# amplifier_modified2.net
KiCad netlist of a schematic drawn in EAGLE
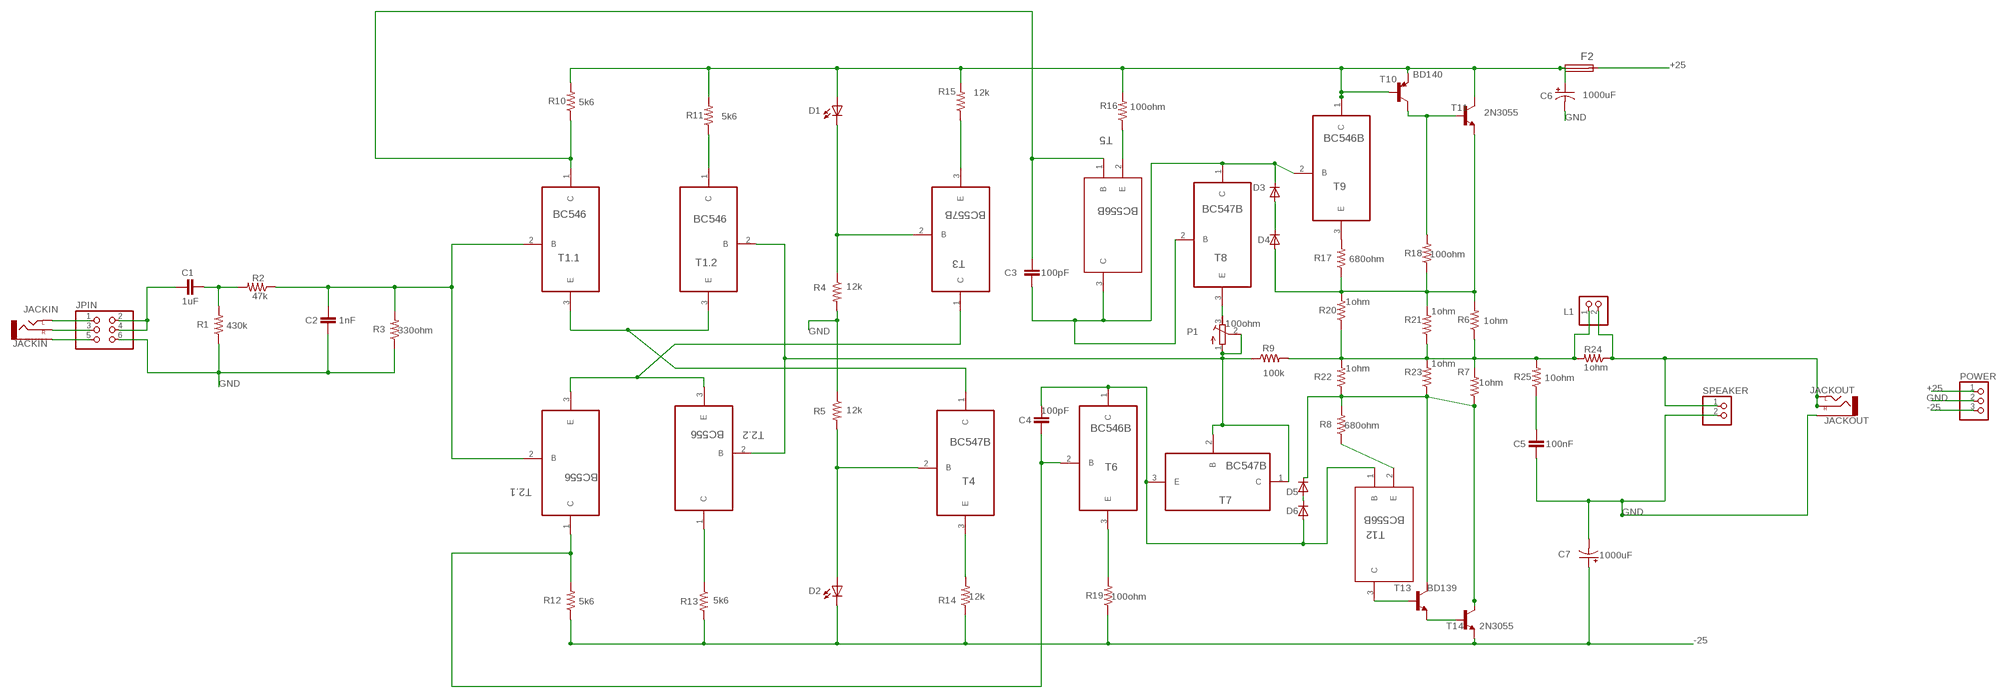
[diagram p0: schematic, sheet 1]

(export (version "E")
  (design (tool "Eeschema 10.0.6"))
  (components
    (comp (ref "C1")
      (value "1uF")
      (footprint "eagle-import:CAP-PTH-5MM")
      (libsource (lib "eagle-import") (part "CAPPTH1"))
    )
    (comp (ref "C2")
      (value "1nF")
      (footprint "eagle-import:CAP-PTH-5MM")
      (libsource (lib "eagle-import") (part "CAPPTH1"))
    )
    (comp (ref "C3")
      (value "100pF")
      (footprint "eagle-import:C5B3")
      (libsource (lib "eagle-import") (part "C5/3"))
    )
    (comp (ref "C4")
      (value "100pF")
      (footprint "eagle-import:C5B3")
      (libsource (lib "eagle-import") (part "C5/3"))
    )
    (comp (ref "C5")
      (value "100nF")
      (footprint "eagle-import:C5B3")
      (libsource (lib "eagle-import") (part "C5/3"))
    )
    (comp (ref "C6")
      (value "1000uF")
      (footprint "eagle-import:E5-6")
      (libsource (lib "eagle-import") (part "CPOL-USE5-6"))
    )
    (comp (ref "C7")
      (value "1000uF")
      (footprint "eagle-import:E5-6")
      (libsource (lib "eagle-import") (part "CPOL-USE5-6"))
    )
    (comp (ref "D1")
      (value "LED5MM")
      (footprint "eagle-import:LED5MM")
      (libsource (lib "eagle-import") (part "LED5MM"))
    )
    (comp (ref "D2")
      (value "LED5MM")
      (footprint "eagle-import:LED5MM")
      (libsource (lib "eagle-import") (part "LED5MM"))
    )
    (comp (ref "D3")
      (value "1N4148DO35-10")
      (footprint "eagle-import:DO35-10")
      (libsource (lib "eagle-import") (part "1N4148DO35-10"))
    )
    (comp (ref "D4")
      (value "1N4148DO35-10")
      (footprint "eagle-import:DO35-10")
      (libsource (lib "eagle-import") (part "1N4148DO35-10"))
    )
    (comp (ref "D5")
      (value "1N4148DO35-10")
      (footprint "eagle-import:DO35-10")
      (libsource (lib "eagle-import") (part "1N4148DO35-10"))
    )
    (comp (ref "D6")
      (value "1N4148DO35-10")
      (footprint "eagle-import:DO35-10")
      (libsource (lib "eagle-import") (part "1N4148DO35-10"))
    )
    (comp (ref "F2")
      (value "FUSEBLANK_5X20MM")
      (footprint "eagle-import:FUSE_HOLDER_5X20MM")
      (fields (field (name "OC_FARNELL") "unknown") (field (name "OC_NEWARK") "unknown"))
      (libsource (lib "eagle-import") (part "FUSEBLANK_5X20MM"))
    )
    (comp (ref "JACKIN")
      (value "JACKIN")
      (footprint "eagle-import:STEREOJACK2.5MM_STEREOJACK2.5MM")
      (libsource (lib "eagle-import") (part "AUDIO-JACK2.5MM"))
    )
    (comp (ref "JACKOUT")
      (value "JACKOUT")
      (footprint "eagle-import:STEREOJACK2.5MM_STEREOJACK2.5MM")
      (libsource (lib "eagle-import") (part "AUDIO-JACK2.5MM"))
    )
    (comp (ref "JPIN")
      (value "PINHD-2X3/90")
      (footprint "eagle-import:2X03_90")
      (libsource (lib "eagle-import") (part "PINHD-2X3/90"))
    )
    (comp (ref "L1")
      (value "PINHD-1X2/90")
      (footprint "eagle-import:1X02_90")
      (libsource (lib "eagle-import") (part "PINHD-1X2/90"))
    )
    (comp (ref "P1")
      (value "100ohm")
      (footprint "eagle-import:RTRIM74X")
      (libsource (lib "eagle-import") (part "R-TRIMM74X"))
    )
    (comp (ref "POWER")
      (value "PINHD-1X3/90")
      (footprint "eagle-import:1X03_90")
      (libsource (lib "eagle-import") (part "PINHD-1X3/90"))
    )
    (comp (ref "R1")
      (value "430k")
      (footprint "eagle-import:AXIAL-0.8")
      (libsource (lib "eagle-import") (part "SparkFun-Resistors_RESISTORPTH-2W"))
    )
    (comp (ref "R2")
      (value "47k")
      (footprint "eagle-import:AXIAL-0.8")
      (libsource (lib "eagle-import") (part "SparkFun-Resistors_RESISTORPTH-2W"))
    )
    (comp (ref "R3")
      (value "330ohm")
      (footprint "eagle-import:AXIAL-0.8")
      (libsource (lib "eagle-import") (part "SparkFun-Resistors_RESISTORPTH-2W"))
    )
    (comp (ref "R4")
      (value "12k")
      (footprint "eagle-import:AXIAL-0.8")
      (libsource (lib "eagle-import") (part "SparkFun-Resistors_RESISTORPTH-2W"))
    )
    (comp (ref "R5")
      (value "12k")
      (footprint "eagle-import:AXIAL-0.8")
      (libsource (lib "eagle-import") (part "SparkFun-Resistors_RESISTORPTH-2W"))
    )
    (comp (ref "R6")
      (value "1ohm")
      (footprint "eagle-import:AXIAL-0.8")
      (libsource (lib "eagle-import") (part "RESISTORPTH-2W"))
    )
    (comp (ref "R7")
      (value "1ohm")
      (footprint "eagle-import:AXIAL-0.8")
      (libsource (lib "eagle-import") (part "RESISTORPTH-2W"))
    )
    (comp (ref "R8")
      (value "680ohm")
      (footprint "eagle-import:AXIAL-0.8")
      (libsource (lib "eagle-import") (part "SparkFun-Resistors_RESISTORPTH-2W"))
    )
    (comp (ref "R9")
      (value "100k")
      (footprint "eagle-import:AXIAL-0.8")
      (libsource (lib "eagle-import") (part "SparkFun-Resistors_RESISTORPTH-2W"))
    )
    (comp (ref "R10")
      (value "5k6")
      (footprint "eagle-import:AXIAL-0.8")
      (libsource (lib "eagle-import") (part "SparkFun-Resistors_RESISTORPTH-2W"))
    )
    (comp (ref "R11")
      (value "5k6")
      (footprint "eagle-import:AXIAL-0.8")
      (libsource (lib "eagle-import") (part "SparkFun-Resistors_RESISTORPTH-2W"))
    )
    (comp (ref "R12")
      (value "5k6")
      (footprint "eagle-import:AXIAL-0.8")
      (libsource (lib "eagle-import") (part "SparkFun-Resistors_RESISTORPTH-2W"))
    )
    (comp (ref "R13")
      (value "5k6")
      (footprint "eagle-import:AXIAL-0.8")
      (libsource (lib "eagle-import") (part "SparkFun-Resistors_RESISTORPTH-2W"))
    )
    (comp (ref "R14")
      (value "12k")
      (footprint "eagle-import:AXIAL-0.8")
      (libsource (lib "eagle-import") (part "SparkFun-Resistors_RESISTORPTH-2W"))
    )
    (comp (ref "R15")
      (value "12k")
      (footprint "eagle-import:AXIAL-0.8")
      (libsource (lib "eagle-import") (part "SparkFun-Resistors_RESISTORPTH-2W"))
    )
    (comp (ref "R16")
      (value "100ohm")
      (footprint "eagle-import:AXIAL-0.8")
      (libsource (lib "eagle-import") (part "SparkFun-Resistors_RESISTORPTH-2W"))
    )
    (comp (ref "R17")
      (value "680ohm")
      (footprint "eagle-import:AXIAL-0.8")
      (libsource (lib "eagle-import") (part "SparkFun-Resistors_RESISTORPTH-2W"))
    )
    (comp (ref "R18")
      (value "100ohm")
      (footprint "eagle-import:AXIAL-0.8")
      (libsource (lib "eagle-import") (part "SparkFun-Resistors_RESISTORPTH-2W"))
    )
    (comp (ref "R19")
      (value "100ohm")
      (footprint "eagle-import:AXIAL-0.8")
      (libsource (lib "eagle-import") (part "SparkFun-Resistors_RESISTORPTH-2W"))
    )
    (comp (ref "R20")
      (value "1ohm")
      (footprint "eagle-import:AXIAL-0.8")
      (libsource (lib "eagle-import") (part "RESISTORPTH-2W"))
    )
    (comp (ref "R21")
      (value "1ohm")
      (footprint "eagle-import:AXIAL-0.8")
      (libsource (lib "eagle-import") (part "RESISTORPTH-2W"))
    )
    (comp (ref "R22")
      (value "1ohm")
      (footprint "eagle-import:AXIAL-0.8")
      (libsource (lib "eagle-import") (part "RESISTORPTH-2W"))
    )
    (comp (ref "R23")
      (value "1ohm")
      (footprint "eagle-import:AXIAL-0.8")
      (libsource (lib "eagle-import") (part "RESISTORPTH-2W"))
    )
    (comp (ref "R24")
      (value "1ohm")
      (footprint "eagle-import:AXIAL-0.8")
      (libsource (lib "eagle-import") (part "RESISTORPTH-2W"))
    )
    (comp (ref "R25")
      (value "10ohm")
      (footprint "eagle-import:AXIAL-0.8")
      (libsource (lib "eagle-import") (part "SparkFun-Resistors_RESISTORPTH-2W"))
    )
    (comp (ref "SPEAKER")
      (value "PINHD-1X2/90")
      (footprint "eagle-import:1X02_90")
      (libsource (lib "eagle-import") (part "PINHD-1X2/90"))
    )
    (comp (ref "T1.1")
      (value "BC546")
      (footprint "eagle-import:TO127P254X732-3")
      (fields (field (name "MPN") "BC546B"))
      (libsource (lib "eagle-import") (part "BC546B"))
    )
    (comp (ref "T1.2")
      (value "BC546")
      (footprint "eagle-import:TO127P254X732-3")
      (fields (field (name "MPN") "BC546B"))
      (libsource (lib "eagle-import") (part "BC546B"))
    )
    (comp (ref "T2.1")
      (value "BC556")
      (footprint "eagle-import:TO127P254X732-3")
      (fields (field (name "MPN") "BC556B"))
      (libsource (lib "eagle-import") (part "BC556B"))
    )
    (comp (ref "T2.2")
      (value "BC556")
      (footprint "eagle-import:TO127P254X732-3")
      (fields (field (name "MPN") "BC556B"))
      (libsource (lib "eagle-import") (part "BC556B"))
    )
    (comp (ref "T3")
      (value "BC557B")
      (footprint "eagle-import:TO127P254X732-3")
      (libsource (lib "eagle-import") (part "BC557B"))
    )
    (comp (ref "T4")
      (value "BC547B")
      (footprint "eagle-import:TO127P254X732-3")
      (libsource (lib "eagle-import") (part "BC547B"))
    )
    (comp (ref "T5")
      (value "BC556B")
      (footprint "eagle-import:SOT95P240X110-3N")
      (fields
        (field (name "MPN") "BC857A")
        (field (name "MPN_1") "BC857A")
        (field (name "OC_FARNELL") "1902487")
        (field (name "OC_NEWARK") "-")
        (field (name "PACKAGE") "SOT-23-3")
        (field (name "SUPPLIER") "DIODES INC.")
      )
      (libsource (lib "eagle-import") (part "BC857A"))
    )
    (comp (ref "T6")
      (value "BC546B")
      (footprint "eagle-import:TO127P254X732-3")
      (libsource (lib "eagle-import") (part "BC546B"))
    )
    (comp (ref "T7")
      (value "BC547B")
      (footprint "eagle-import:TO127P254X732-3")
      (libsource (lib "eagle-import") (part "BC547B"))
    )
    (comp (ref "T8")
      (value "BC547B")
      (footprint "eagle-import:TO127P254X732-3")
      (libsource (lib "eagle-import") (part "BC547B"))
    )
    (comp (ref "T9")
      (value "BC546B")
      (footprint "eagle-import:TO127P254X732-3")
      (libsource (lib "eagle-import") (part "BC546B"))
    )
    (comp (ref "T10")
      (value "BD140")
      (footprint "eagle-import:TO126")
      (libsource (lib "eagle-import") (part "BD140"))
    )
    (comp (ref "T11")
      (value "2N3055")
      (footprint "eagle-import:TO3")
      (libsource (lib "eagle-import") (part "2N3055"))
    )
    (comp (ref "T12")
      (value "BC556B")
      (footprint "eagle-import:SOT95P240X110-3N")
      (fields
        (field (name "MPN") "BC857A")
        (field (name "MPN_1") "BC857A")
        (field (name "OC_FARNELL") "1902487")
        (field (name "OC_NEWARK") "-")
        (field (name "PACKAGE") "SOT-23-3")
        (field (name "SUPPLIER") "DIODES INC.")
      )
      (libsource (lib "eagle-import") (part "BC857A"))
    )
    (comp (ref "T13")
      (value "BD139")
      (footprint "eagle-import:TO126")
      (libsource (lib "eagle-import") (part "BD139"))
    )
    (comp (ref "T14")
      (value "2N3055")
      (footprint "eagle-import:TO3")
      (libsource (lib "eagle-import") (part "2N3055"))
    )
  )
  (nets
    (net (code "1") (name "/+25") (class "Default")
      (node (ref "F2") (pin "2") (pinfunction "2_2") (pintype "passive"))
      (node (ref "POWER") (pin "1") (pinfunction "1_1") (pintype "passive"))
    )
    (net (code "2") (name "/-25") (class "Default")
      (node (ref "C7") (pin "+") (pinfunction "+_+") (pintype "passive"))
      (node (ref "D2") (pin "K") (pinfunction "C_K") (pintype "passive"))
      (node (ref "POWER") (pin "3") (pinfunction "3_3") (pintype "passive"))
      (node (ref "R12") (pin "P$1") (pinfunction "1_P$1") (pintype "passive"))
      (node (ref "R13") (pin "P$2") (pinfunction "2_P$2") (pintype "passive"))
      (node (ref "R14") (pin "P$1") (pinfunction "1_P$1") (pintype "passive"))
      (node (ref "R19") (pin "P$1") (pinfunction "1_P$1") (pintype "passive"))
      (node (ref "T14") (pin "E") (pinfunction "E_E") (pintype "passive"))
    )
    (net (code "3") (name "/GND") (class "Default")
      (node (ref "C2") (pin "1") (pinfunction "1_1") (pintype "passive"))
      (node (ref "C5") (pin "1") (pinfunction "1_1") (pintype "passive"))
      (node (ref "C6") (pin "-") (pinfunction "-_-") (pintype "passive"))
      (node (ref "C7") (pin "-") (pinfunction "-_-") (pintype "passive"))
      (node (ref "JACKOUT") (pin "RING1") (pinfunction "SLEEVE_RING1") (pintype "bidirectional"))
      (node (ref "JPIN") (pin "6") (pinfunction "6_6") (pintype "passive"))
      (node (ref "POWER") (pin "2") (pinfunction "2_2") (pintype "passive"))
      (node (ref "R1") (pin "P$1") (pinfunction "1_P$1") (pintype "passive"))
      (node (ref "R3") (pin "P$1") (pinfunction "1_P$1") (pintype "passive"))
      (node (ref "R4") (pin "P$2") (pinfunction "2_P$2") (pintype "passive"))
      (node (ref "R5") (pin "P$1") (pinfunction "1_P$1") (pintype "passive"))
      (node (ref "SPEAKER") (pin "2") (pinfunction "2_2") (pintype "passive"))
    )
    (net (code "4") (name "Net-(C1-Pad1)") (class "Default")
      (node (ref "C1") (pin "1") (pinfunction "1_1") (pintype "passive"))
      (node (ref "JPIN") (pin "2") (pinfunction "2_2") (pintype "passive"))
      (node (ref "JPIN") (pin "4") (pinfunction "4_4") (pintype "passive"))
    )
    (net (code "5") (name "Net-(D1-C)") (class "Default")
      (node (ref "D1") (pin "K") (pinfunction "C_K") (pintype "passive"))
      (node (ref "R4") (pin "P$1") (pinfunction "1_P$1") (pintype "passive"))
      (node (ref "T3") (pin "2") (pinfunction "B_2") (pintype "passive"))
    )
    (net (code "6") (name "Net-(D3-PadA)") (class "Default")
      (node (ref "D3") (pin "A") (pinfunction "A_A") (pintype "passive"))
      (node (ref "D4") (pin "C") (pinfunction "C_C") (pintype "passive"))
    )
    (net (code "7") (name "Net-(D5-PadA)") (class "Default")
      (node (ref "D5") (pin "A") (pinfunction "A_A") (pintype "passive"))
      (node (ref "D6") (pin "C") (pinfunction "C_C") (pintype "passive"))
    )
    (net (code "8") (name "Net-(JACKIN-LEFT)") (class "Default")
      (node (ref "JACKIN") (pin "SHIELD") (pinfunction "LEFT_SHIELD") (pintype "bidirectional"))
      (node (ref "JPIN") (pin "1") (pinfunction "1_1") (pintype "passive"))
    )
    (net (code "9") (name "Net-(JACKIN-RIGHT)") (class "Default")
      (node (ref "JACKIN") (pin "TIP") (pinfunction "RIGHT_TIP") (pintype "bidirectional"))
      (node (ref "JPIN") (pin "3") (pinfunction "3_3") (pintype "passive"))
    )
    (net (code "10") (name "Net-(JACKIN-SLEEVE)") (class "Default")
      (node (ref "JACKIN") (pin "RING1") (pinfunction "SLEEVE_RING1") (pintype "bidirectional"))
      (node (ref "JPIN") (pin "5") (pinfunction "5_5") (pintype "passive"))
    )
    (net (code "11") (name "Net-(JACKOUT-LEFT)") (class "Default")
      (node (ref "JACKOUT") (pin "SHIELD") (pinfunction "LEFT_SHIELD") (pintype "bidirectional"))
      (node (ref "JACKOUT") (pin "TIP") (pinfunction "RIGHT_TIP") (pintype "bidirectional"))
      (node (ref "L1") (pin "2") (pinfunction "2_2") (pintype "passive"))
      (node (ref "R24") (pin "P$1") (pinfunction "1_P$1") (pintype "passive"))
      (node (ref "SPEAKER") (pin "1") (pinfunction "1_1") (pintype "passive"))
    )
    (net (code "12") (name "Net-(P1-A)") (class "Default")
      (node (ref "P1") (pin "1") (pinfunction "A_1") (pintype "passive"))
      (node (ref "P1") (pin "2") (pinfunction "S_2") (pintype "passive"))
      (node (ref "R9") (pin "P$1") (pinfunction "1_P$1") (pintype "passive"))
      (node (ref "T1.2") (pin "2") (pinfunction "B_2") (pintype "passive"))
      (node (ref "T2.2") (pin "2") (pinfunction "B_2") (pintype "passive"))
      (node (ref "T7") (pin "1") (pinfunction "C_1") (pintype "passive"))
      (node (ref "T7") (pin "2") (pinfunction "B_2") (pintype "passive"))
    )
    (net (code "13") (name "Net-(P1-E)") (class "Default")
      (node (ref "P1") (pin "3") (pinfunction "E_3") (pintype "passive"))
      (node (ref "T8") (pin "3") (pinfunction "E_3") (pintype "passive"))
    )
    (net (code "14") (name "Net-(R1-2)") (class "Default")
      (node (ref "C1") (pin "2") (pinfunction "2_2") (pintype "passive"))
      (node (ref "R1") (pin "P$2") (pinfunction "2_P$2") (pintype "passive"))
      (node (ref "R2") (pin "P$2") (pinfunction "2_P$2") (pintype "passive"))
    )
    (net (code "15") (name "Net-(R2-1)") (class "Default")
      (node (ref "C2") (pin "2") (pinfunction "2_2") (pintype "passive"))
      (node (ref "R2") (pin "P$1") (pinfunction "1_P$1") (pintype "passive"))
      (node (ref "R3") (pin "P$2") (pinfunction "2_P$2") (pintype "passive"))
      (node (ref "T1.1") (pin "2") (pinfunction "B_2") (pintype "passive"))
      (node (ref "T2.1") (pin "2") (pinfunction "B_2") (pintype "passive"))
    )
    (net (code "16") (name "Net-(R5-2)") (class "Default")
      (node (ref "D2") (pin "A") (pinfunction "A_A") (pintype "passive"))
      (node (ref "R5") (pin "P$2") (pinfunction "2_P$2") (pintype "passive"))
      (node (ref "T4") (pin "2") (pinfunction "B_2") (pintype "passive"))
    )
    (net (code "17") (name "Net-(R8-1)") (class "Default")
      (node (ref "R8") (pin "P$1") (pinfunction "1_P$1") (pintype "passive"))
      (node (ref "T12") (pin "2") (pinfunction "E_2") (pintype "passive"))
    )
    (net (code "18") (name "Net-(R10-1)") (class "Default")
      (node (ref "C3") (pin "2") (pinfunction "2_2") (pintype "passive"))
      (node (ref "R10") (pin "P$1") (pinfunction "1_P$1") (pintype "passive"))
      (node (ref "T1.1") (pin "1") (pinfunction "C_1") (pintype "passive"))
      (node (ref "T5") (pin "1") (pinfunction "B_1") (pintype "passive"))
    )
    (net (code "19") (name "Net-(R10-2)") (class "Default")
      (node (ref "C6") (pin "+") (pinfunction "+_+") (pintype "passive"))
      (node (ref "D1") (pin "A") (pinfunction "A_A") (pintype "passive"))
      (node (ref "F2") (pin "1") (pinfunction "1_1") (pintype "passive"))
      (node (ref "R10") (pin "P$2") (pinfunction "2_P$2") (pintype "passive"))
      (node (ref "R11") (pin "P$2") (pinfunction "2_P$2") (pintype "passive"))
      (node (ref "R15") (pin "P$2") (pinfunction "2_P$2") (pintype "passive"))
      (node (ref "R16") (pin "P$2") (pinfunction "2_P$2") (pintype "passive"))
      (node (ref "T10") (pin "1") (pinfunction "E_1") (pintype "passive"))
      (node (ref "T10") (pin "3") (pinfunction "B_3") (pintype "passive"))
      (node (ref "T11") (pin "C") (pinfunction "C_C") (pintype "passive"))
      (node (ref "T11") (pin "C/") (pinfunction "C_C/") (pintype "passive"))
      (node (ref "T9") (pin "1") (pinfunction "C_1") (pintype "passive"))
    )
    (net (code "20") (name "Net-(R11-1)") (class "Default")
      (node (ref "R11") (pin "P$1") (pinfunction "1_P$1") (pintype "passive"))
      (node (ref "T1.2") (pin "1") (pinfunction "C_1") (pintype "passive"))
    )
    (net (code "21") (name "Net-(R12-2)") (class "Default")
      (node (ref "C4") (pin "1") (pinfunction "1_1") (pintype "passive"))
      (node (ref "R12") (pin "P$2") (pinfunction "2_P$2") (pintype "passive"))
      (node (ref "T2.1") (pin "1") (pinfunction "C_1") (pintype "passive"))
      (node (ref "T6") (pin "2") (pinfunction "B_2") (pintype "passive"))
    )
    (net (code "22") (name "Net-(R13-1)") (class "Default")
      (node (ref "R13") (pin "P$1") (pinfunction "1_P$1") (pintype "passive"))
      (node (ref "T2.2") (pin "1") (pinfunction "C_1") (pintype "passive"))
    )
    (net (code "23") (name "Net-(R14-2)") (class "Default")
      (node (ref "R14") (pin "P$2") (pinfunction "2_P$2") (pintype "passive"))
      (node (ref "T4") (pin "3") (pinfunction "E_3") (pintype "passive"))
    )
    (net (code "24") (name "Net-(R15-1)") (class "Default")
      (node (ref "R15") (pin "P$1") (pinfunction "1_P$1") (pintype "passive"))
      (node (ref "T3") (pin "3") (pinfunction "E_3") (pintype "passive"))
    )
    (net (code "25") (name "Net-(R16-1)") (class "Default")
      (node (ref "R16") (pin "P$1") (pinfunction "1_P$1") (pintype "passive"))
      (node (ref "T5") (pin "2") (pinfunction "E_2") (pintype "passive"))
    )
    (net (code "26") (name "Net-(R17-1)") (class "Default")
      (node (ref "D4") (pin "A") (pinfunction "A_A") (pintype "passive"))
      (node (ref "R17") (pin "P$1") (pinfunction "1_P$1") (pintype "passive"))
      (node (ref "R18") (pin "P$1") (pinfunction "1_P$1") (pintype "passive"))
      (node (ref "R20") (pin "P$2") (pinfunction "2_P$2") (pintype "passive"))
      (node (ref "R21") (pin "P$2") (pinfunction "2_P$2") (pintype "passive"))
      (node (ref "R6") (pin "P$2") (pinfunction "2_P$2") (pintype "passive"))
      (node (ref "T11") (pin "E") (pinfunction "E_E") (pintype "passive"))
    )
    (net (code "27") (name "Net-(R17-2)") (class "Default")
      (node (ref "R17") (pin "P$2") (pinfunction "2_P$2") (pintype "passive"))
      (node (ref "T9") (pin "3") (pinfunction "E_3") (pintype "passive"))
    )
    (net (code "28") (name "Net-(R18-2)") (class "Default")
      (node (ref "R18") (pin "P$2") (pinfunction "2_P$2") (pintype "passive"))
      (node (ref "T10") (pin "2") (pinfunction "C_2") (pintype "passive"))
      (node (ref "T11") (pin "B") (pinfunction "B_B") (pintype "passive"))
    )
    (net (code "29") (name "Net-(R19-2)") (class "Default")
      (node (ref "R19") (pin "P$2") (pinfunction "2_P$2") (pintype "passive"))
      (node (ref "T6") (pin "3") (pinfunction "E_3") (pintype "passive"))
    )
    (net (code "30") (name "Net-(R20-1)") (class "Default")
      (node (ref "L1") (pin "1") (pinfunction "1_1") (pintype "passive"))
      (node (ref "R20") (pin "P$1") (pinfunction "1_P$1") (pintype "passive"))
      (node (ref "R21") (pin "P$1") (pinfunction "1_P$1") (pintype "passive"))
      (node (ref "R22") (pin "P$2") (pinfunction "2_P$2") (pintype "passive"))
      (node (ref "R23") (pin "P$2") (pinfunction "2_P$2") (pintype "passive"))
      (node (ref "R24") (pin "P$2") (pinfunction "2_P$2") (pintype "passive"))
      (node (ref "R25") (pin "P$2") (pinfunction "2_P$2") (pintype "passive"))
      (node (ref "R6") (pin "P$1") (pinfunction "1_P$1") (pintype "passive"))
      (node (ref "R7") (pin "P$2") (pinfunction "2_P$2") (pintype "passive"))
      (node (ref "R9") (pin "P$2") (pinfunction "2_P$2") (pintype "passive"))
    )
    (net (code "31") (name "Net-(R22-1)") (class "Default")
      (node (ref "D5") (pin "C") (pinfunction "C_C") (pintype "passive"))
      (node (ref "R22") (pin "P$1") (pinfunction "1_P$1") (pintype "passive"))
      (node (ref "R23") (pin "P$1") (pinfunction "1_P$1") (pintype "passive"))
      (node (ref "R7") (pin "P$1") (pinfunction "1_P$1") (pintype "passive"))
      (node (ref "R8") (pin "P$2") (pinfunction "2_P$2") (pintype "passive"))
      (node (ref "T13") (pin "2") (pinfunction "C_2") (pintype "passive"))
      (node (ref "T14") (pin "C") (pinfunction "C_C") (pintype "passive"))
      (node (ref "T14") (pin "C/") (pinfunction "C_C/") (pintype "passive"))
    )
    (net (code "32") (name "Net-(R25-1)") (class "Default")
      (node (ref "C5") (pin "2") (pinfunction "2_2") (pintype "passive"))
      (node (ref "R25") (pin "P$1") (pinfunction "1_P$1") (pintype "passive"))
    )
    (net (code "33") (name "Net-(T1.1-E)") (class "Default")
      (node (ref "T1.1") (pin "3") (pinfunction "E_3") (pintype "passive"))
      (node (ref "T1.2") (pin "3") (pinfunction "E_3") (pintype "passive"))
      (node (ref "T4") (pin "1") (pinfunction "C_1") (pintype "passive"))
    )
    (net (code "34") (name "Net-(T2.1-E)") (class "Default")
      (node (ref "T2.1") (pin "3") (pinfunction "E_3") (pintype "passive"))
      (node (ref "T2.2") (pin "3") (pinfunction "E_3") (pintype "passive"))
      (node (ref "T3") (pin "1") (pinfunction "C_1") (pintype "passive"))
    )
    (net (code "35") (name "Net-(T5-C)") (class "Default")
      (node (ref "C3") (pin "1") (pinfunction "1_1") (pintype "passive"))
      (node (ref "D3") (pin "C") (pinfunction "C_C") (pintype "passive"))
      (node (ref "T5") (pin "3") (pinfunction "C_3") (pintype "passive"))
      (node (ref "T8") (pin "1") (pinfunction "C_1") (pintype "passive"))
      (node (ref "T8") (pin "2") (pinfunction "B_2") (pintype "passive"))
      (node (ref "T9") (pin "2") (pinfunction "B_2") (pintype "passive"))
    )
    (net (code "36") (name "Net-(T12-B)") (class "Default")
      (node (ref "C4") (pin "2") (pinfunction "2_2") (pintype "passive"))
      (node (ref "D6") (pin "A") (pinfunction "A_A") (pintype "passive"))
      (node (ref "T12") (pin "1") (pinfunction "B_1") (pintype "passive"))
      (node (ref "T6") (pin "1") (pinfunction "C_1") (pintype "passive"))
      (node (ref "T7") (pin "3") (pinfunction "E_3") (pintype "passive"))
    )
    (net (code "37") (name "Net-(T12-C)") (class "Default")
      (node (ref "T12") (pin "3") (pinfunction "C_3") (pintype "passive"))
      (node (ref "T13") (pin "3") (pinfunction "B_3") (pintype "passive"))
    )
    (net (code "38") (name "Net-(T13-E)") (class "Default")
      (node (ref "T13") (pin "1") (pinfunction "E_1") (pintype "passive"))
      (node (ref "T14") (pin "B") (pinfunction "B_B") (pintype "passive"))
    )
  )
)
